# 16-DPLL_Spare_UFL.net
KiCad netlist of a schematic drawn in Altium Designer
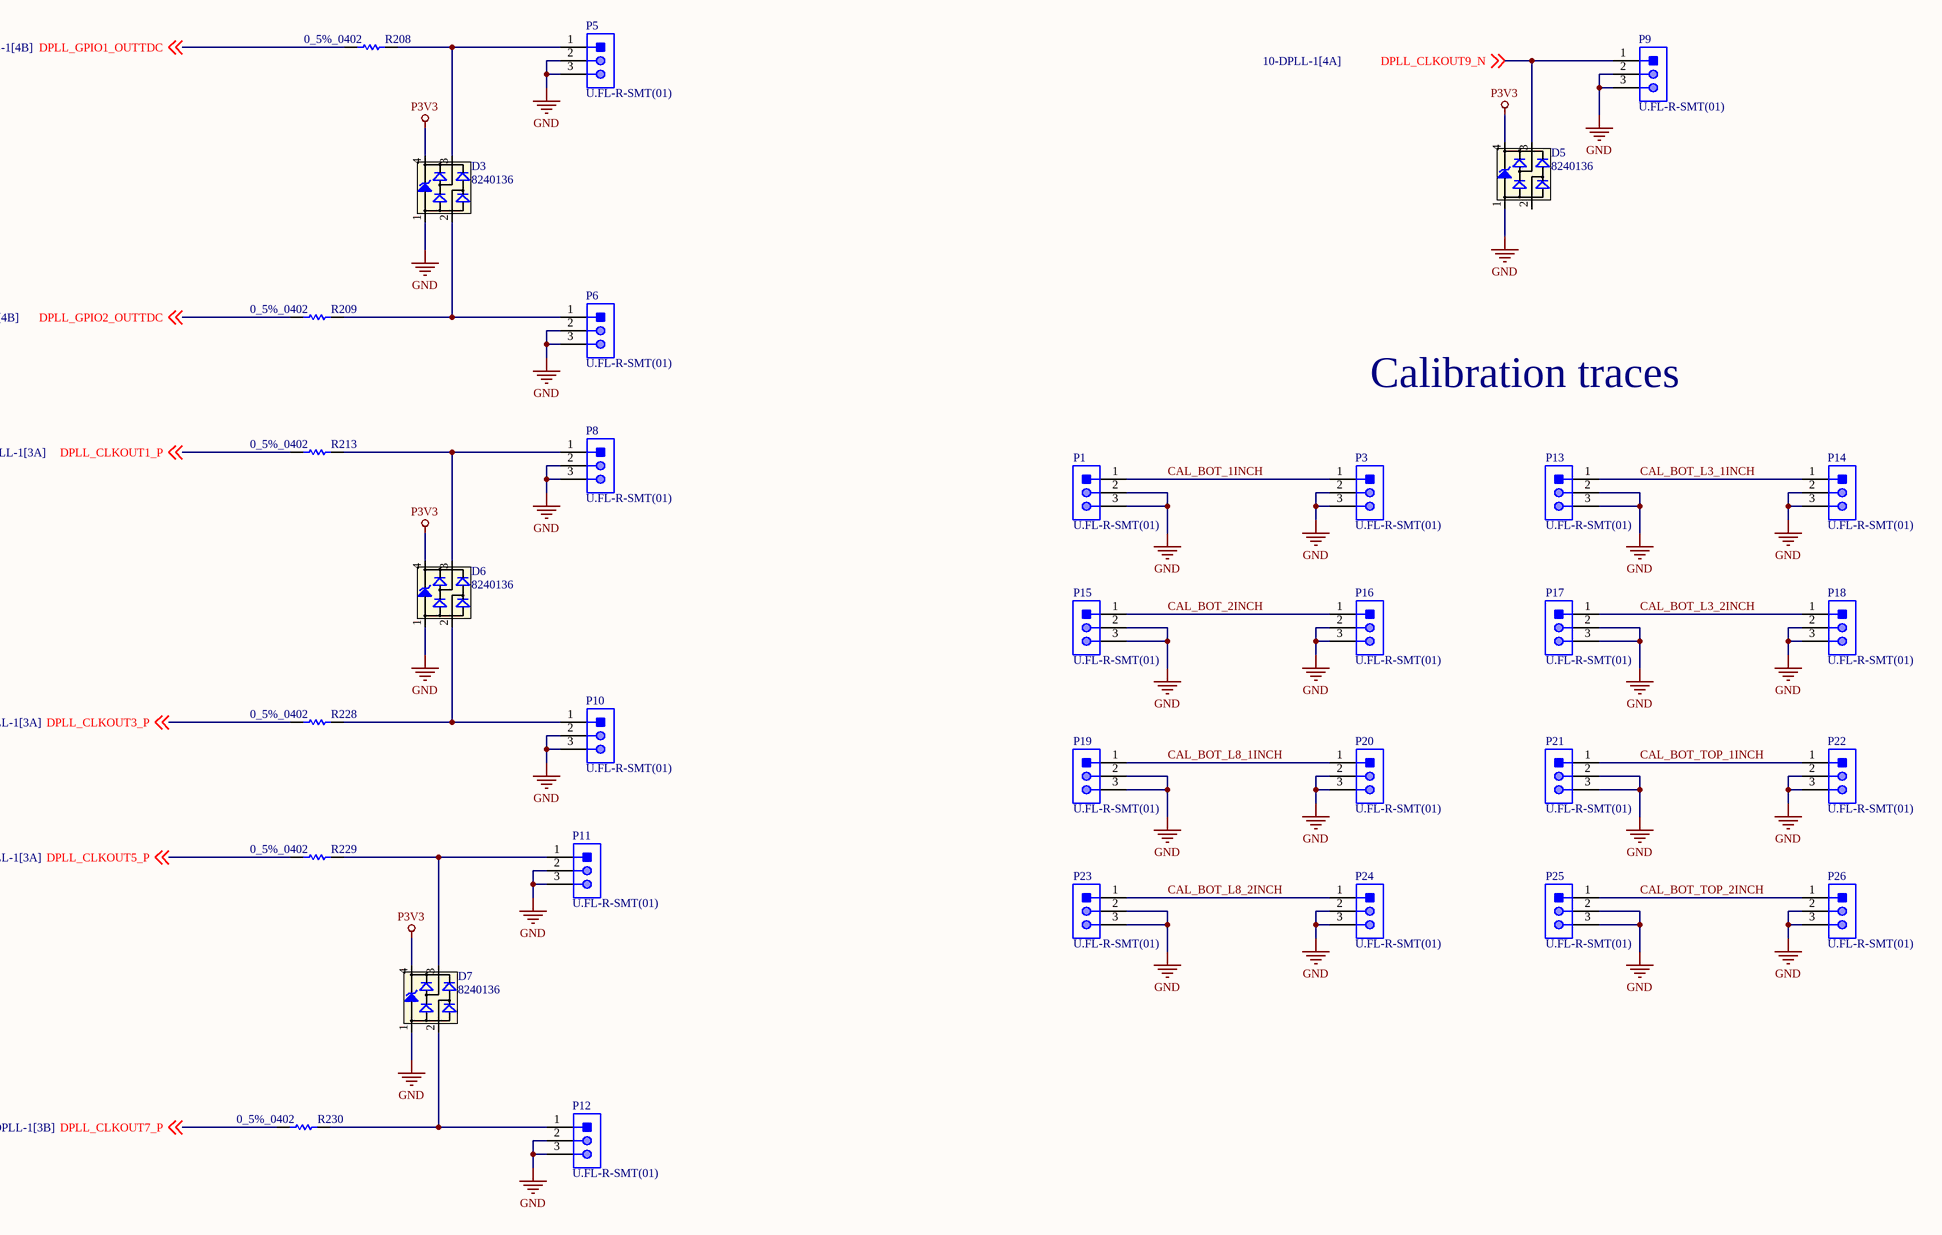
[diagram p0: 16-DPLL_Spare_UFL.SchDoc]

(export (version "E")
  (design (tool "Eeschema 10.0.6"))
  (components
    (comp (ref "D3")
      (value "8240136")
      (footprint "SOT143-4L")
      (description "TVS Diode WE-TVS-HS, VRWM=3.3V")
      (fields (field (name "MANUFACTURER") "Wuerth Elektronik"))
      (libsource (lib "Altium Content Vault") (part "WE-TVS-HS-4"))
    )
    (comp (ref "D5")
      (value "8240136")
      (footprint "SOT143-4L")
      (description "TVS Diode WE-TVS-HS, VRWM=3.3V")
      (fields (field (name "MANUFACTURER") "Wuerth Elektronik"))
      (libsource (lib "Altium Content Vault") (part "WE-TVS-HS-4"))
    )
    (comp (ref "D6")
      (value "8240136")
      (footprint "SOT143-4L")
      (description "TVS Diode WE-TVS-HS, VRWM=3.3V")
      (fields (field (name "MANUFACTURER") "Wuerth Elektronik"))
      (libsource (lib "Altium Content Vault") (part "WE-TVS-HS-4"))
    )
    (comp (ref "D7")
      (value "8240136")
      (footprint "SOT143-4L")
      (description "TVS Diode WE-TVS-HS, VRWM=3.3V")
      (fields (field (name "MANUFACTURER") "Wuerth Elektronik"))
      (libsource (lib "Altium Content Vault") (part "WE-TVS-HS-4"))
    )
    (comp (ref "P1")
      (value "U.FL-R-SMT(01)")
      (footprint "HRS-U.FL-R-SMT(10)_V")
      (description "CONN RECPT ULTRA-MINI COAX SMD")
      (fields (field (name "MANUFACTURER") "Hirose Electric") (field (name "APPROVAL CATEGORY") "UL94V-0"))
      (libsource (lib "Altium Content Vault") (part "CN-1P-M-R3"))
    )
    (comp (ref "P3")
      (value "U.FL-R-SMT(01)")
      (footprint "HRS-U.FL-R-SMT(10)_V")
      (description "CONN RECPT ULTRA-MINI COAX SMD")
      (fields (field (name "MANUFACTURER") "Hirose Electric") (field (name "APPROVAL CATEGORY") "UL94V-0"))
      (libsource (lib "") (part "CN-1P-M-R3_1"))
    )
    (comp (ref "P5")
      (value "U.FL-R-SMT(01)")
      (footprint "HRS-U.FL-R-SMT(10)_V")
      (description "CONN RECPT ULTRA-MINI COAX SMD")
      (fields (field (name "MANUFACTURER") "Hirose Electric") (field (name "APPROVAL CATEGORY") "UL94V-0"))
      (libsource (lib "") (part "CN-1P-M-R3_1"))
    )
    (comp (ref "P6")
      (value "U.FL-R-SMT(01)")
      (footprint "HRS-U.FL-R-SMT(10)_V")
      (description "CONN RECPT ULTRA-MINI COAX SMD")
      (fields (field (name "MANUFACTURER") "Hirose Electric") (field (name "APPROVAL CATEGORY") "UL94V-0"))
      (libsource (lib "") (part "CN-1P-M-R3_1"))
    )
    (comp (ref "P8")
      (value "U.FL-R-SMT(01)")
      (footprint "HRS-U.FL-R-SMT(10)_V")
      (description "CONN RECPT ULTRA-MINI COAX SMD")
      (fields (field (name "MANUFACTURER") "Hirose Electric") (field (name "APPROVAL CATEGORY") "UL94V-0"))
      (libsource (lib "") (part "CN-1P-M-R3_1"))
    )
    (comp (ref "P9")
      (value "U.FL-R-SMT(01)")
      (footprint "HRS-U.FL-R-SMT(10)_V")
      (description "CONN RECPT ULTRA-MINI COAX SMD")
      (fields (field (name "MANUFACTURER") "Hirose Electric") (field (name "APPROVAL CATEGORY") "UL94V-0"))
      (libsource (lib "") (part "CN-1P-M-R3_1"))
    )
    (comp (ref "P10")
      (value "U.FL-R-SMT(01)")
      (footprint "HRS-U.FL-R-SMT(10)_V")
      (description "CONN RECPT ULTRA-MINI COAX SMD")
      (fields (field (name "MANUFACTURER") "Hirose Electric") (field (name "APPROVAL CATEGORY") "UL94V-0"))
      (libsource (lib "") (part "CN-1P-M-R3_1"))
    )
    (comp (ref "P11")
      (value "U.FL-R-SMT(01)")
      (footprint "HRS-U.FL-R-SMT(10)_V")
      (description "CONN RECPT ULTRA-MINI COAX SMD")
      (fields (field (name "MANUFACTURER") "Hirose Electric") (field (name "APPROVAL CATEGORY") "UL94V-0"))
      (libsource (lib "") (part "CN-1P-M-R3_1"))
    )
    (comp (ref "P12")
      (value "U.FL-R-SMT(01)")
      (footprint "HRS-U.FL-R-SMT(10)_V")
      (description "CONN RECPT ULTRA-MINI COAX SMD")
      (fields (field (name "MANUFACTURER") "Hirose Electric") (field (name "APPROVAL CATEGORY") "UL94V-0"))
      (libsource (lib "") (part "CN-1P-M-R3_1"))
    )
    (comp (ref "P13")
      (value "U.FL-R-SMT(01)")
      (footprint "HRS-U.FL-R-SMT(10)_V")
      (description "CONN RECPT ULTRA-MINI COAX SMD")
      (fields (field (name "MANUFACTURER") "Hirose Electric") (field (name "APPROVAL CATEGORY") "UL94V-0"))
      (libsource (lib "Altium Content Vault") (part "CN-1P-M-R3"))
    )
    (comp (ref "P14")
      (value "U.FL-R-SMT(01)")
      (footprint "HRS-U.FL-R-SMT(10)_V")
      (description "CONN RECPT ULTRA-MINI COAX SMD")
      (fields (field (name "MANUFACTURER") "Hirose Electric") (field (name "APPROVAL CATEGORY") "UL94V-0"))
      (libsource (lib "") (part "CN-1P-M-R3_1"))
    )
    (comp (ref "P15")
      (value "U.FL-R-SMT(01)")
      (footprint "HRS-U.FL-R-SMT(10)_V")
      (description "CONN RECPT ULTRA-MINI COAX SMD")
      (fields (field (name "MANUFACTURER") "Hirose Electric") (field (name "APPROVAL CATEGORY") "UL94V-0"))
      (libsource (lib "Altium Content Vault") (part "CN-1P-M-R3"))
    )
    (comp (ref "P16")
      (value "U.FL-R-SMT(01)")
      (footprint "HRS-U.FL-R-SMT(10)_V")
      (description "CONN RECPT ULTRA-MINI COAX SMD")
      (fields (field (name "MANUFACTURER") "Hirose Electric") (field (name "APPROVAL CATEGORY") "UL94V-0"))
      (libsource (lib "") (part "CN-1P-M-R3_1"))
    )
    (comp (ref "P17")
      (value "U.FL-R-SMT(01)")
      (footprint "HRS-U.FL-R-SMT(10)_V")
      (description "CONN RECPT ULTRA-MINI COAX SMD")
      (fields (field (name "MANUFACTURER") "Hirose Electric") (field (name "APPROVAL CATEGORY") "UL94V-0"))
      (libsource (lib "Altium Content Vault") (part "CN-1P-M-R3"))
    )
    (comp (ref "P18")
      (value "U.FL-R-SMT(01)")
      (footprint "HRS-U.FL-R-SMT(10)_V")
      (description "CONN RECPT ULTRA-MINI COAX SMD")
      (fields (field (name "MANUFACTURER") "Hirose Electric") (field (name "APPROVAL CATEGORY") "UL94V-0"))
      (libsource (lib "") (part "CN-1P-M-R3_1"))
    )
    (comp (ref "P19")
      (value "U.FL-R-SMT(01)")
      (footprint "HRS-U.FL-R-SMT(10)_V")
      (description "CONN RECPT ULTRA-MINI COAX SMD")
      (fields (field (name "MANUFACTURER") "Hirose Electric") (field (name "APPROVAL CATEGORY") "UL94V-0"))
      (libsource (lib "Altium Content Vault") (part "CN-1P-M-R3"))
    )
    (comp (ref "P20")
      (value "U.FL-R-SMT(01)")
      (footprint "HRS-U.FL-R-SMT(10)_V")
      (description "CONN RECPT ULTRA-MINI COAX SMD")
      (fields (field (name "MANUFACTURER") "Hirose Electric") (field (name "APPROVAL CATEGORY") "UL94V-0"))
      (libsource (lib "") (part "CN-1P-M-R3_1"))
    )
    (comp (ref "P21")
      (value "U.FL-R-SMT(01)")
      (footprint "HRS-U.FL-R-SMT(10)_V")
      (description "CONN RECPT ULTRA-MINI COAX SMD")
      (fields (field (name "MANUFACTURER") "Hirose Electric") (field (name "APPROVAL CATEGORY") "UL94V-0"))
      (libsource (lib "Altium Content Vault") (part "CN-1P-M-R3"))
    )
    (comp (ref "P22")
      (value "U.FL-R-SMT(01)")
      (footprint "HRS-U.FL-R-SMT(10)_V")
      (description "CONN RECPT ULTRA-MINI COAX SMD")
      (fields (field (name "MANUFACTURER") "Hirose Electric") (field (name "APPROVAL CATEGORY") "UL94V-0"))
      (libsource (lib "") (part "CN-1P-M-R3_1"))
    )
    (comp (ref "P23")
      (value "U.FL-R-SMT(01)")
      (footprint "HRS-U.FL-R-SMT(10)_V")
      (description "CONN RECPT ULTRA-MINI COAX SMD")
      (fields (field (name "MANUFACTURER") "Hirose Electric") (field (name "APPROVAL CATEGORY") "UL94V-0"))
      (libsource (lib "Altium Content Vault") (part "CN-1P-M-R3"))
    )
    (comp (ref "P24")
      (value "U.FL-R-SMT(01)")
      (footprint "HRS-U.FL-R-SMT(10)_V")
      (description "CONN RECPT ULTRA-MINI COAX SMD")
      (fields (field (name "MANUFACTURER") "Hirose Electric") (field (name "APPROVAL CATEGORY") "UL94V-0"))
      (libsource (lib "") (part "CN-1P-M-R3_1"))
    )
    (comp (ref "P25")
      (value "U.FL-R-SMT(01)")
      (footprint "HRS-U.FL-R-SMT(10)_V")
      (description "CONN RECPT ULTRA-MINI COAX SMD")
      (fields (field (name "MANUFACTURER") "Hirose Electric") (field (name "APPROVAL CATEGORY") "UL94V-0"))
      (libsource (lib "Altium Content Vault") (part "CN-1P-M-R3"))
    )
    (comp (ref "P26")
      (value "U.FL-R-SMT(01)")
      (footprint "HRS-U.FL-R-SMT(10)_V")
      (description "CONN RECPT ULTRA-MINI COAX SMD")
      (fields (field (name "MANUFACTURER") "Hirose Electric") (field (name "APPROVAL CATEGORY") "UL94V-0"))
      (libsource (lib "") (part "CN-1P-M-R3_1"))
    )
    (comp (ref "R208")
      (value "0_5%_0402")
      (footprint "RESC1005X40X25LL10T10")
      (fields (field (name "MANUFACTURER") "KOA Speer") (field (name "PART NUMBER") "RK73Z1ETTP"))
      (libsource (lib "Altium Content Vault") (part "RES"))
    )
    (comp (ref "R209")
      (value "0_5%_0402")
      (footprint "RESC1005X40X25LL10T10")
      (fields (field (name "MANUFACTURER") "KOA Speer") (field (name "PART NUMBER") "RK73Z1ETTP"))
      (libsource (lib "Altium Content Vault") (part "RES"))
    )
    (comp (ref "R213")
      (value "0_5%_0402")
      (footprint "RESC1005X40X25LL10T10")
      (fields (field (name "MANUFACTURER") "KOA Speer") (field (name "PART NUMBER") "RK73Z1ETTP"))
      (libsource (lib "Altium Content Vault") (part "RES"))
    )
    (comp (ref "R228")
      (value "0_5%_0402")
      (footprint "RESC1005X40X25LL10T10")
      (fields (field (name "MANUFACTURER") "KOA Speer") (field (name "PART NUMBER") "RK73Z1ETTP"))
      (libsource (lib "Altium Content Vault") (part "RES"))
    )
    (comp (ref "R229")
      (value "0_5%_0402")
      (footprint "RESC1005X40X25LL10T10")
      (fields (field (name "MANUFACTURER") "KOA Speer") (field (name "PART NUMBER") "RK73Z1ETTP"))
      (libsource (lib "Altium Content Vault") (part "RES"))
    )
    (comp (ref "R230")
      (value "0_5%_0402")
      (footprint "RESC1005X40X25LL10T10")
      (fields (field (name "MANUFACTURER") "KOA Speer") (field (name "PART NUMBER") "RK73Z1ETTP"))
      (libsource (lib "Altium Content Vault") (part "RES"))
    )
  )
  (nets
    (net (code "1") (name "/CAL_BOT_1INCH") (class "Default")
      (node (ref "P1") (pin "1") (pinfunction "1_1") (pintype "passive"))
      (node (ref "P3") (pin "1") (pinfunction "1_1") (pintype "passive"))
    )
    (net (code "2") (name "/CAL_BOT_2INCH") (class "Default")
      (node (ref "P15") (pin "1") (pinfunction "1_1") (pintype "passive"))
      (node (ref "P16") (pin "1") (pinfunction "1_1") (pintype "passive"))
    )
    (net (code "3") (name "/CAL_BOT_L3_1INCH") (class "Default")
      (node (ref "P13") (pin "1") (pinfunction "1_1") (pintype "passive"))
      (node (ref "P14") (pin "1") (pinfunction "1_1") (pintype "passive"))
    )
    (net (code "4") (name "/CAL_BOT_L3_2INCH") (class "Default")
      (node (ref "P17") (pin "1") (pinfunction "1_1") (pintype "passive"))
      (node (ref "P18") (pin "1") (pinfunction "1_1") (pintype "passive"))
    )
    (net (code "5") (name "/CAL_BOT_L8_1INCH") (class "Default")
      (node (ref "P19") (pin "1") (pinfunction "1_1") (pintype "passive"))
      (node (ref "P20") (pin "1") (pinfunction "1_1") (pintype "passive"))
    )
    (net (code "6") (name "/CAL_BOT_L8_2INCH") (class "Default")
      (node (ref "P23") (pin "1") (pinfunction "1_1") (pintype "passive"))
      (node (ref "P24") (pin "1") (pinfunction "1_1") (pintype "passive"))
    )
    (net (code "7") (name "/CAL_BOT_TOP_1INCH") (class "Default")
      (node (ref "P21") (pin "1") (pinfunction "1_1") (pintype "passive"))
      (node (ref "P22") (pin "1") (pinfunction "1_1") (pintype "passive"))
    )
    (net (code "8") (name "/CAL_BOT_TOP_2INCH") (class "Default")
      (node (ref "P25") (pin "1") (pinfunction "1_1") (pintype "passive"))
      (node (ref "P26") (pin "1") (pinfunction "1_1") (pintype "passive"))
    )
    (net (code "9") (name "DPLL_CLKOUT1_P") (class "Default")
      (node (ref "R213") (pin "1") (pinfunction "1_1") (pintype "passive"))
    )
    (net (code "10") (name "DPLL_CLKOUT3_P") (class "Default")
      (node (ref "R228") (pin "1") (pinfunction "1_1") (pintype "passive"))
    )
    (net (code "11") (name "DPLL_CLKOUT5_P") (class "Default")
      (node (ref "R229") (pin "1") (pinfunction "1_1") (pintype "passive"))
    )
    (net (code "12") (name "DPLL_CLKOUT7_P") (class "Default")
      (node (ref "R230") (pin "1") (pinfunction "1_1") (pintype "passive"))
    )
    (net (code "13") (name "DPLL_CLKOUT9_N") (class "Default")
      (node (ref "D5") (pin "3") (pinfunction "I/O2_3") (pintype "passive"))
      (node (ref "P9") (pin "1") (pinfunction "1_1") (pintype "passive"))
    )
    (net (code "14") (name "DPLL_GPIO1_OUTTDC") (class "Default")
      (node (ref "R208") (pin "1") (pinfunction "1_1") (pintype "passive"))
    )
    (net (code "15") (name "DPLL_GPIO2_OUTTDC") (class "Default")
      (node (ref "R209") (pin "1") (pinfunction "1_1") (pintype "passive"))
    )
    (net (code "16") (name "GND") (class "Default")
      (node (ref "D3") (pin "1") (pinfunction "GND_1") (pintype "passive"))
      (node (ref "D5") (pin "1") (pinfunction "GND_1") (pintype "passive"))
      (node (ref "D6") (pin "1") (pinfunction "GND_1") (pintype "passive"))
      (node (ref "D7") (pin "1") (pinfunction "GND_1") (pintype "passive"))
      (node (ref "P1") (pin "2") (pinfunction "2_2") (pintype "passive"))
      (node (ref "P1") (pin "3") (pinfunction "3_3") (pintype "passive"))
      (node (ref "P10") (pin "2") (pinfunction "2_2") (pintype "passive"))
      (node (ref "P10") (pin "3") (pinfunction "3_3") (pintype "passive"))
      (node (ref "P11") (pin "2") (pinfunction "2_2") (pintype "passive"))
      (node (ref "P11") (pin "3") (pinfunction "3_3") (pintype "passive"))
      (node (ref "P12") (pin "2") (pinfunction "2_2") (pintype "passive"))
      (node (ref "P12") (pin "3") (pinfunction "3_3") (pintype "passive"))
      (node (ref "P13") (pin "2") (pinfunction "2_2") (pintype "passive"))
      (node (ref "P13") (pin "3") (pinfunction "3_3") (pintype "passive"))
      (node (ref "P14") (pin "2") (pinfunction "2_2") (pintype "passive"))
      (node (ref "P14") (pin "3") (pinfunction "3_3") (pintype "passive"))
      (node (ref "P15") (pin "2") (pinfunction "2_2") (pintype "passive"))
      (node (ref "P15") (pin "3") (pinfunction "3_3") (pintype "passive"))
      (node (ref "P16") (pin "2") (pinfunction "2_2") (pintype "passive"))
      (node (ref "P16") (pin "3") (pinfunction "3_3") (pintype "passive"))
      (node (ref "P17") (pin "2") (pinfunction "2_2") (pintype "passive"))
      (node (ref "P17") (pin "3") (pinfunction "3_3") (pintype "passive"))
      (node (ref "P18") (pin "2") (pinfunction "2_2") (pintype "passive"))
      (node (ref "P18") (pin "3") (pinfunction "3_3") (pintype "passive"))
      (node (ref "P19") (pin "2") (pinfunction "2_2") (pintype "passive"))
      (node (ref "P19") (pin "3") (pinfunction "3_3") (pintype "passive"))
      (node (ref "P20") (pin "2") (pinfunction "2_2") (pintype "passive"))
      (node (ref "P20") (pin "3") (pinfunction "3_3") (pintype "passive"))
      (node (ref "P21") (pin "2") (pinfunction "2_2") (pintype "passive"))
      (node (ref "P21") (pin "3") (pinfunction "3_3") (pintype "passive"))
      (node (ref "P22") (pin "2") (pinfunction "2_2") (pintype "passive"))
      (node (ref "P22") (pin "3") (pinfunction "3_3") (pintype "passive"))
      (node (ref "P23") (pin "2") (pinfunction "2_2") (pintype "passive"))
      (node (ref "P23") (pin "3") (pinfunction "3_3") (pintype "passive"))
      (node (ref "P24") (pin "2") (pinfunction "2_2") (pintype "passive"))
      (node (ref "P24") (pin "3") (pinfunction "3_3") (pintype "passive"))
      (node (ref "P25") (pin "2") (pinfunction "2_2") (pintype "passive"))
      (node (ref "P25") (pin "3") (pinfunction "3_3") (pintype "passive"))
      (node (ref "P26") (pin "2") (pinfunction "2_2") (pintype "passive"))
      (node (ref "P26") (pin "3") (pinfunction "3_3") (pintype "passive"))
      (node (ref "P3") (pin "2") (pinfunction "2_2") (pintype "passive"))
      (node (ref "P3") (pin "3") (pinfunction "3_3") (pintype "passive"))
      (node (ref "P5") (pin "2") (pinfunction "2_2") (pintype "passive"))
      (node (ref "P5") (pin "3") (pinfunction "3_3") (pintype "passive"))
      (node (ref "P6") (pin "2") (pinfunction "2_2") (pintype "passive"))
      (node (ref "P6") (pin "3") (pinfunction "3_3") (pintype "passive"))
      (node (ref "P8") (pin "2") (pinfunction "2_2") (pintype "passive"))
      (node (ref "P8") (pin "3") (pinfunction "3_3") (pintype "passive"))
      (node (ref "P9") (pin "2") (pinfunction "2_2") (pintype "passive"))
      (node (ref "P9") (pin "3") (pinfunction "3_3") (pintype "passive"))
    )
    (net (code "17") (name "Net-(D3-I{slash}O1)") (class "Default")
      (node (ref "D3") (pin "2") (pinfunction "I/O1_2") (pintype "passive"))
      (node (ref "P6") (pin "1") (pinfunction "1_1") (pintype "passive"))
      (node (ref "R209") (pin "2") (pinfunction "2_2") (pintype "passive"))
    )
    (net (code "18") (name "Net-(D3-I{slash}O2)") (class "Default")
      (node (ref "D3") (pin "3") (pinfunction "I/O2_3") (pintype "passive"))
      (node (ref "P5") (pin "1") (pinfunction "1_1") (pintype "passive"))
      (node (ref "R208") (pin "2") (pinfunction "2_2") (pintype "passive"))
    )
    (net (code "19") (name "Net-(D6-I{slash}O1)") (class "Default")
      (node (ref "D6") (pin "2") (pinfunction "I/O1_2") (pintype "passive"))
      (node (ref "P10") (pin "1") (pinfunction "1_1") (pintype "passive"))
      (node (ref "R228") (pin "2") (pinfunction "2_2") (pintype "passive"))
    )
    (net (code "20") (name "Net-(D6-I{slash}O2)") (class "Default")
      (node (ref "D6") (pin "3") (pinfunction "I/O2_3") (pintype "passive"))
      (node (ref "P8") (pin "1") (pinfunction "1_1") (pintype "passive"))
      (node (ref "R213") (pin "2") (pinfunction "2_2") (pintype "passive"))
    )
    (net (code "21") (name "Net-(D7-I{slash}O1)") (class "Default")
      (node (ref "D7") (pin "2") (pinfunction "I/O1_2") (pintype "passive"))
      (node (ref "P12") (pin "1") (pinfunction "1_1") (pintype "passive"))
      (node (ref "R230") (pin "2") (pinfunction "2_2") (pintype "passive"))
    )
    (net (code "22") (name "Net-(D7-I{slash}O2)") (class "Default")
      (node (ref "D7") (pin "3") (pinfunction "I/O2_3") (pintype "passive"))
      (node (ref "P11") (pin "1") (pinfunction "1_1") (pintype "passive"))
      (node (ref "R229") (pin "2") (pinfunction "2_2") (pintype "passive"))
    )
    (net (code "23") (name "P3V3") (class "Default")
      (node (ref "D3") (pin "4") (pinfunction "VDD_4") (pintype "passive"))
      (node (ref "D5") (pin "4") (pinfunction "VDD_4") (pintype "passive"))
      (node (ref "D6") (pin "4") (pinfunction "VDD_4") (pintype "passive"))
      (node (ref "D7") (pin "4") (pinfunction "VDD_4") (pintype "passive"))
    )
    (net (code "24") (name "unconnected-(D5-I{slash}O1-Pad2)") (class "Default")
      (node (ref "D5") (pin "2") (pinfunction "I/O1_2") (pintype "passive"))
    )
  )
)
